# hand_rev_1_3_c.net
KiCad netlist of a schematic drawn in EAGLE
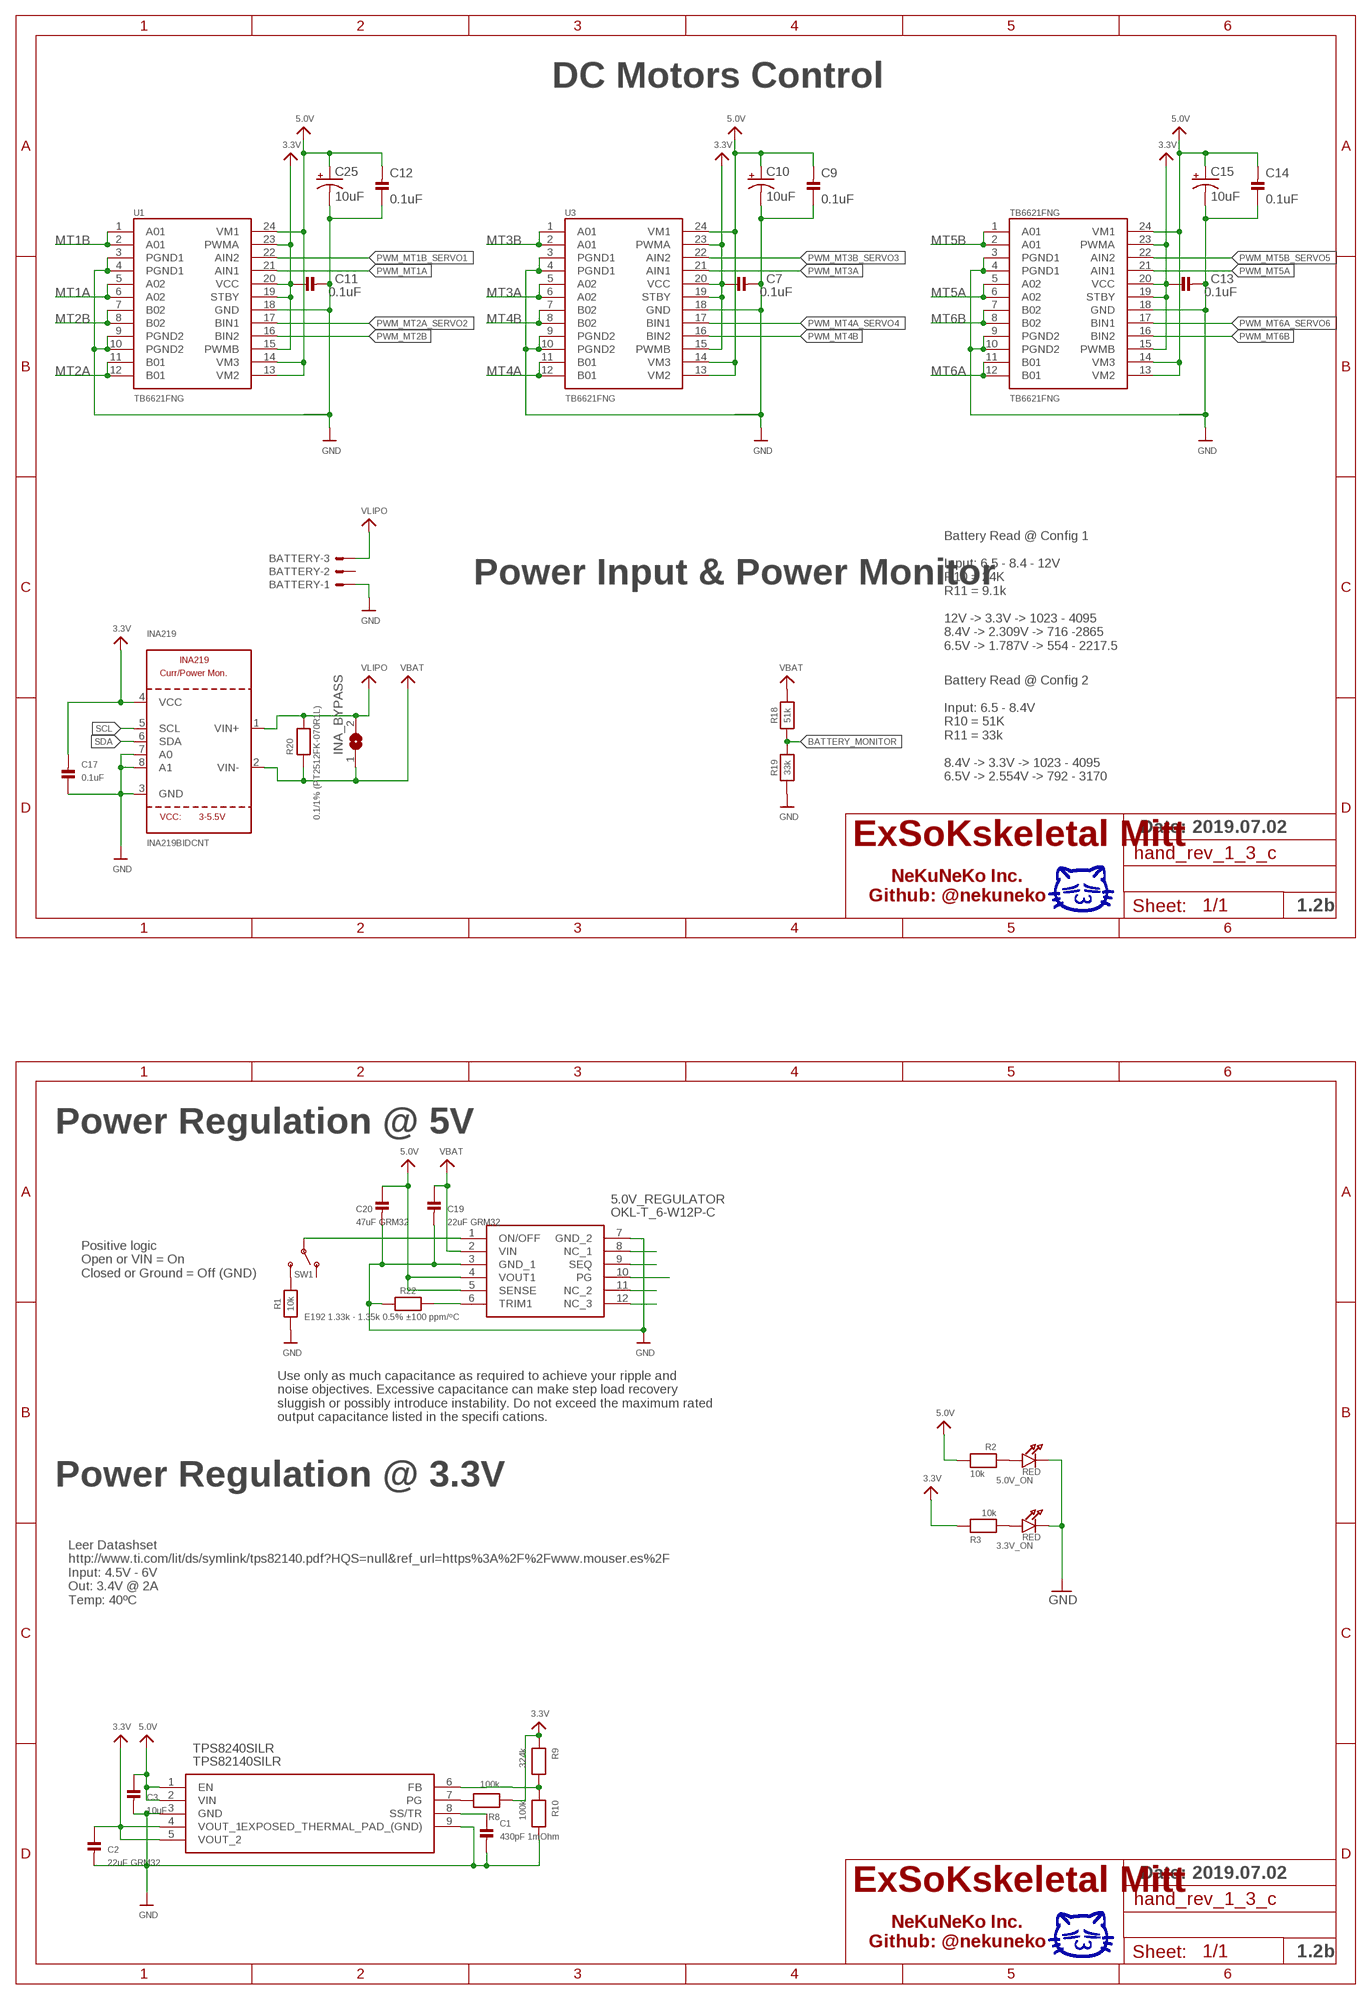
[diagram p0: schematic, sheet 1, part 1 of 2]
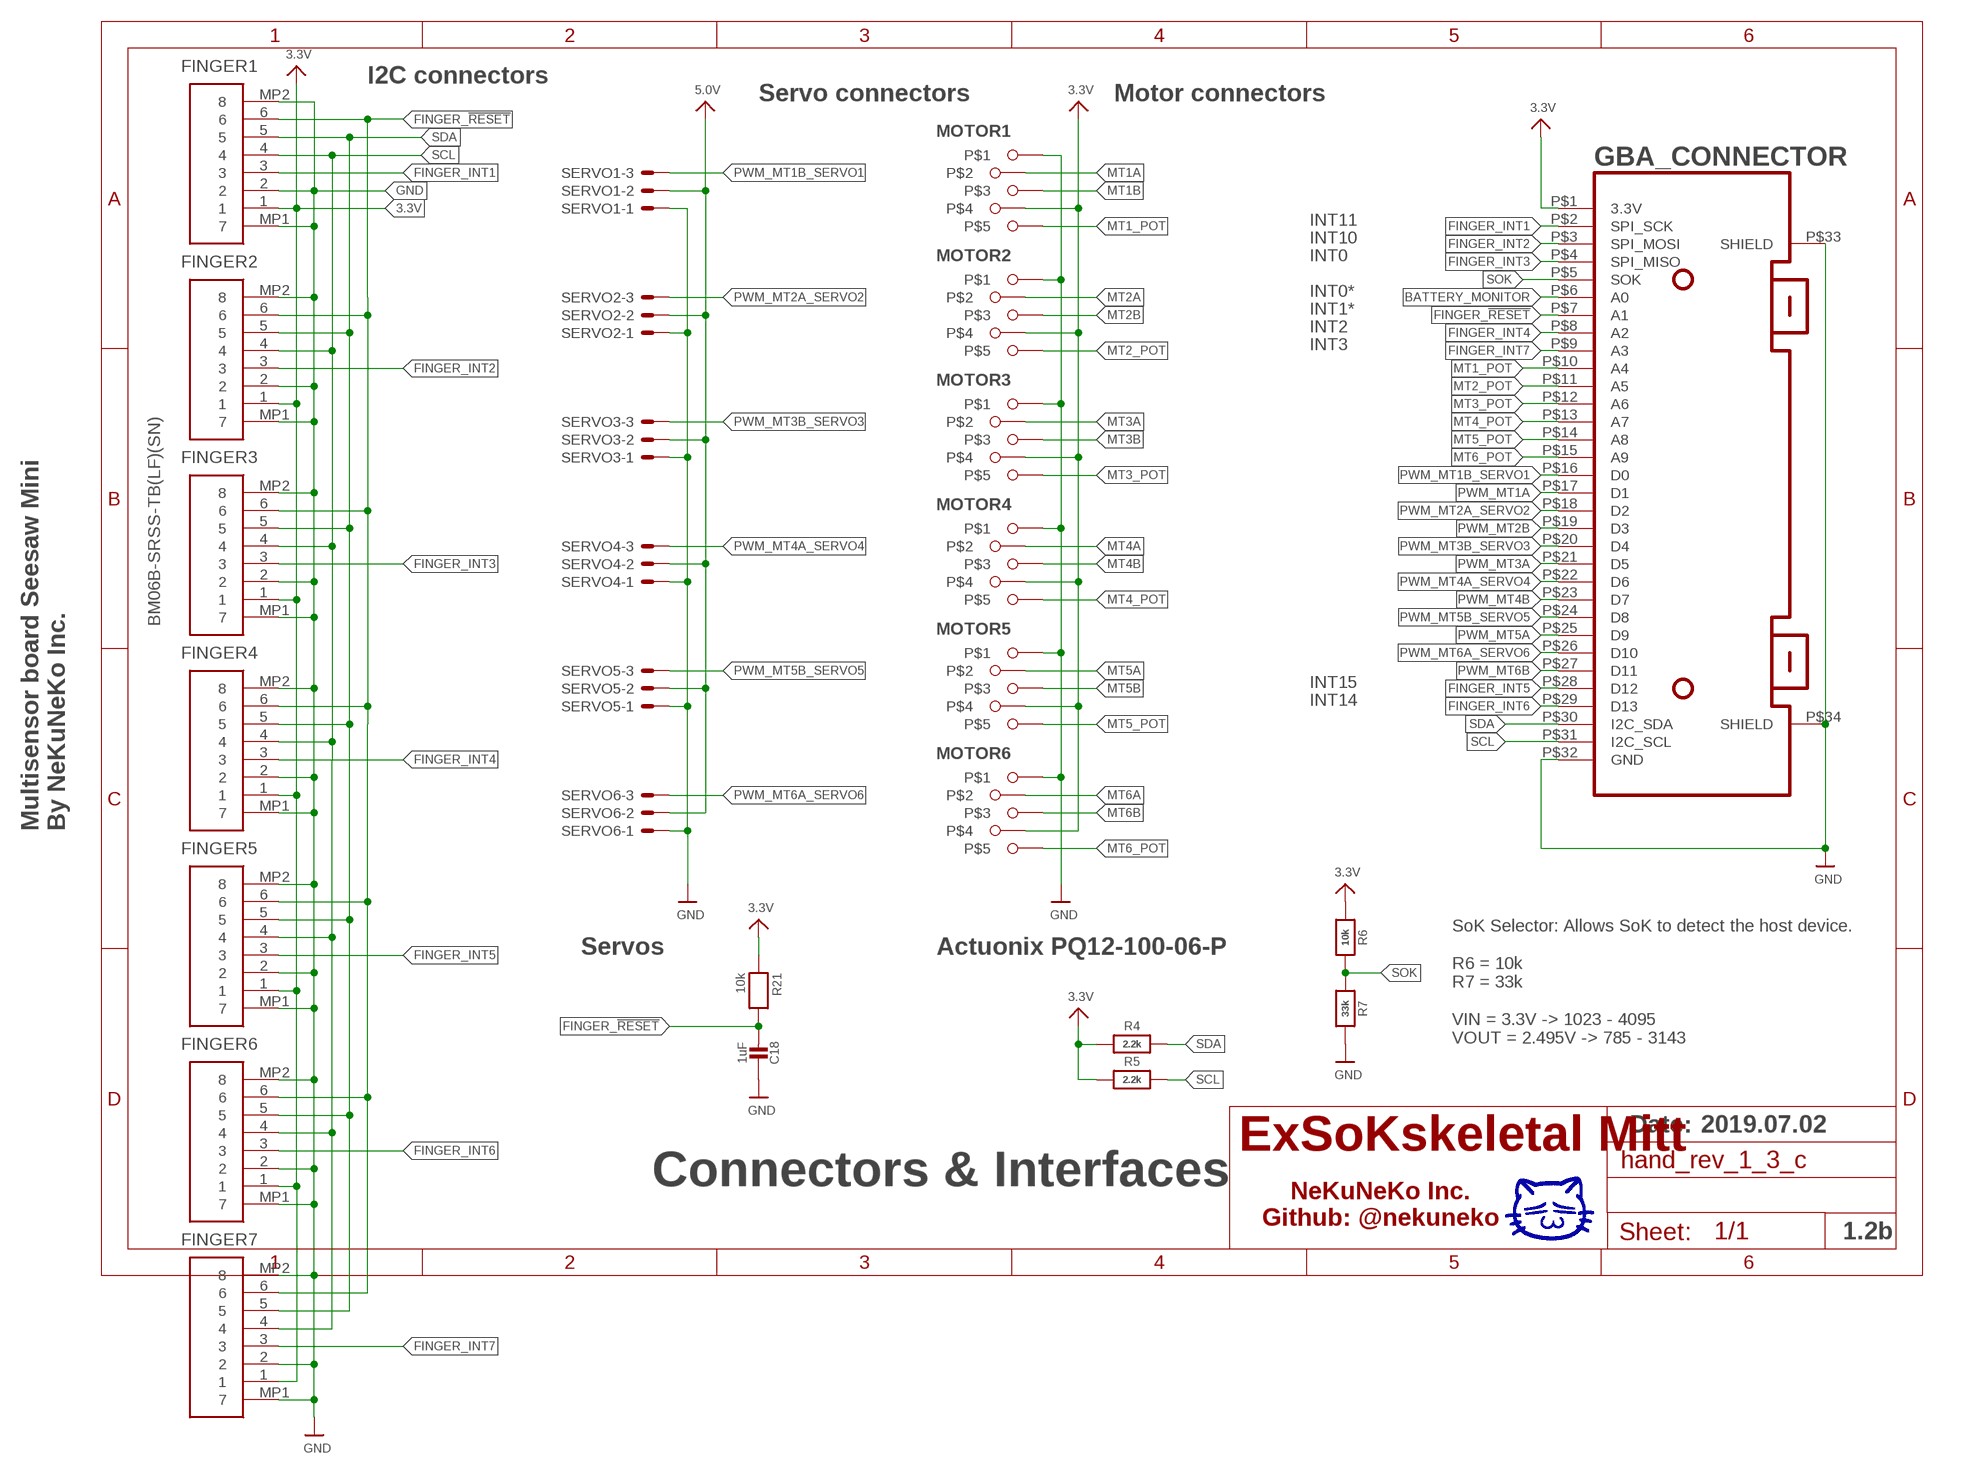
[diagram p1: schematic, sheet 1, part 2 of 2]

(export (version "E")
  (design (tool "Eeschema 10.0.6"))
  (components
    (comp (ref "3.3V_ON")
      (value "RED")
      (footprint "eagle-import:CHIPLED_0603")
      (libsource (lib "eagle-import") (part "LED0603"))
    )
    (comp (ref "5.0V_ON")
      (value "RED")
      (footprint "eagle-import:CHIPLED_0603")
      (libsource (lib "eagle-import") (part "LED0603"))
    )
    (comp (ref "5.0V_REGULATOR")
      (value "OKL-T_6-W12P-C")
      (footprint "eagle-import:OKL-T3-W12")
      (fields
        (field (name "MANUFACTURER_PART_NUMBER") "OKL-T/6-W12P-C")
        (field (name "MOUSER_PART_NUMBER") "580-OKL-T/6-W12P-C")
      )
      (libsource (lib "eagle-import") (part "OKL-T_6-W12P-C"))
    )
    (comp (ref "BATTERY")
      (value "JST-XH-03-PIN-LONG-PAD")
      (footprint "eagle-import:JST-XH-03-PACKAGE-LONG-PAD")
      (libsource (lib "eagle-import") (part "JST-XH-03-PIN-LONG-PAD"))
    )
    (comp (ref "C1")
      (value "430pF 1mOhm")
      (footprint "eagle-import:_0402")
      (libsource (lib "eagle-import") (part "microbuilder_CAP_CERAMIC_0402"))
    )
    (comp (ref "C2")
      (value "22uF GRM32")
      (footprint "eagle-import:_0603")
      (libsource (lib "eagle-import") (part "microbuilder_CAP_CERAMIC_0603"))
    )
    (comp (ref "C3")
      (value "10uF")
      (footprint "eagle-import:_0603")
      (libsource (lib "eagle-import") (part "microbuilder_CAP_CERAMIC_0603"))
    )
    (comp (ref "C7")
      (value "0.1uF")
      (footprint "eagle-import:_0603")
      (libsource (lib "eagle-import") (part "microbuilder_CAP_CERAMIC_0603"))
    )
    (comp (ref "C9")
      (value "0.1uF")
      (footprint "eagle-import:_0603")
      (libsource (lib "eagle-import") (part "microbuilder_CAP_CERAMIC_0603"))
    )
    (comp (ref "C10")
      (value "10uF")
      (footprint "eagle-import:0603-POLAR")
      (fields (field (name "MPN") "F981A106MMA"))
      (libsource (lib "eagle-import") (part "10UF-POLAR-0603-6.3V-20%(TANT)"))
    )
    (comp (ref "C11")
      (value "0.1uF")
      (footprint "eagle-import:_0603")
      (libsource (lib "eagle-import") (part "microbuilder_CAP_CERAMIC_0603"))
    )
    (comp (ref "C12")
      (value "0.1uF")
      (footprint "eagle-import:_0603")
      (libsource (lib "eagle-import") (part "microbuilder_CAP_CERAMIC_0603"))
    )
    (comp (ref "C13")
      (value "0.1uF")
      (footprint "eagle-import:_0603")
      (libsource (lib "eagle-import") (part "microbuilder_CAP_CERAMIC_0603"))
    )
    (comp (ref "C14")
      (value "0.1uF")
      (footprint "eagle-import:_0603")
      (libsource (lib "eagle-import") (part "microbuilder_CAP_CERAMIC_0603"))
    )
    (comp (ref "C15")
      (value "10uF")
      (footprint "eagle-import:0603-POLAR")
      (fields (field (name "MPN") "F981A106MMA"))
      (libsource (lib "eagle-import") (part "10UF-POLAR-0603-6.3V-20%(TANT)"))
    )
    (comp (ref "C17")
      (value "0.1uF")
      (footprint "eagle-import:_0603")
      (libsource (lib "eagle-import") (part "microbuilder_CAP_CERAMIC_0603"))
    )
    (comp (ref "C18")
      (value "1uF")
      (footprint "eagle-import:MICROBUILDER__0603")
      (libsource (lib "eagle-import") (part "CAP_CERAMIC_0603"))
    )
    (comp (ref "C19")
      (value "22uF GRM32")
      (footprint "eagle-import:0805")
      (libsource (lib "eagle-import") (part "CAP_CERAMIC0805"))
    )
    (comp (ref "C20")
      (value "47uF GRM32")
      (footprint "eagle-import:0805")
      (libsource (lib "eagle-import") (part "CAP_CERAMIC0805"))
    )
    (comp (ref "C25")
      (value "10uF")
      (footprint "eagle-import:0603-POLAR")
      (fields (field (name "MPN") "F981A106MMA"))
      (libsource (lib "eagle-import") (part "10UF-POLAR-0603-6.3V-20%(TANT)"))
    )
    (comp (ref "FINGER1")
      (value "BM06B-SRSS-TB(LF)(SN)")
      (footprint "eagle-import:BM06BSRSSTBLFSN")
      (fields (field (name "RS_PART_NUMBER") "5468782"))
      (libsource (lib "eagle-import") (part "BM06B-SRSS-TB(LF)(SN)"))
    )
    (comp (ref "FINGER2")
      (value "BM06B-SRSS-TB(LF)(SN)")
      (footprint "eagle-import:BM06BSRSSTBLFSN")
      (fields (field (name "RS_PART_NUMBER") "5468782"))
      (libsource (lib "eagle-import") (part "BM06B-SRSS-TB(LF)(SN)"))
    )
    (comp (ref "FINGER3")
      (value "BM06B-SRSS-TB(LF)(SN)")
      (footprint "eagle-import:BM06BSRSSTBLFSN")
      (fields (field (name "RS_PART_NUMBER") "5468782"))
      (libsource (lib "eagle-import") (part "BM06B-SRSS-TB(LF)(SN)"))
    )
    (comp (ref "FINGER4")
      (value "BM06B-SRSS-TB(LF)(SN)")
      (footprint "eagle-import:BM06BSRSSTBLFSN")
      (fields (field (name "RS_PART_NUMBER") "5468782"))
      (libsource (lib "eagle-import") (part "BM06B-SRSS-TB(LF)(SN)"))
    )
    (comp (ref "FINGER5")
      (value "BM06B-SRSS-TB(LF)(SN)")
      (footprint "eagle-import:BM06BSRSSTBLFSN")
      (fields (field (name "RS_PART_NUMBER") "5468782"))
      (libsource (lib "eagle-import") (part "BM06B-SRSS-TB(LF)(SN)"))
    )
    (comp (ref "FINGER6")
      (value "BM06B-SRSS-TB(LF)(SN)")
      (footprint "eagle-import:BM06BSRSSTBLFSN")
      (fields (field (name "RS_PART_NUMBER") "5468782"))
      (libsource (lib "eagle-import") (part "BM06B-SRSS-TB(LF)(SN)"))
    )
    (comp (ref "FINGER7")
      (value "BM06B-SRSS-TB(LF)(SN)")
      (footprint "eagle-import:BM06BSRSSTBLFSN")
      (fields (field (name "RS_PART_NUMBER") "5468782"))
      (libsource (lib "eagle-import") (part "BM06B-SRSS-TB(LF)(SN)"))
    )
    (comp (ref "GBA_CONNECTOR")
      (value "GBA_CARTRIDGEGBA_CARTRIDGE2")
      (footprint "eagle-import:GBA_CARTRIDGE2")
      (libsource (lib "eagle-import") (part "GBA_CARTRIDGEGBA_CARTRIDGE2"))
    )
    (comp (ref "INA219")
      (value "INA219BIDCNT")
      (footprint "eagle-import:SOT23-8")
      (libsource (lib "eagle-import") (part "INA219"))
    )
    (comp (ref "INA_BYPASS")
      (value "SOLDERJUMPERREFLOW_NOPASTE")
      (footprint "eagle-import:SOLDERJUMPER_REFLOW_NOPASTE")
      (libsource (lib "eagle-import") (part "SOLDERJUMPERREFLOW_NOPASTE"))
    )
    (comp (ref "MOTOR1")
      (value "Actuonix PQ12-100-06-P")
      (footprint "eagle-import:5PIN")
      (libsource (lib "eagle-import") (part "5PIN"))
    )
    (comp (ref "MOTOR2")
      (value "Actuonix PQ12-100-06-P")
      (footprint "eagle-import:5PIN")
      (libsource (lib "eagle-import") (part "5PIN"))
    )
    (comp (ref "MOTOR3")
      (value "Actuonix PQ12-100-06-P")
      (footprint "eagle-import:5PIN")
      (libsource (lib "eagle-import") (part "5PIN"))
    )
    (comp (ref "MOTOR4")
      (value "Actuonix PQ12-100-06-P")
      (footprint "eagle-import:5PIN")
      (libsource (lib "eagle-import") (part "5PIN"))
    )
    (comp (ref "MOTOR5")
      (value "Actuonix PQ12-100-06-P")
      (footprint "eagle-import:5PIN")
      (libsource (lib "eagle-import") (part "5PIN"))
    )
    (comp (ref "MOTOR6")
      (value "Actuonix PQ12-100-06-P")
      (footprint "eagle-import:5PIN")
      (libsource (lib "eagle-import") (part "5PIN"))
    )
    (comp (ref "R1")
      (value "10k")
      (footprint "eagle-import:_0603")
      (libsource (lib "eagle-import") (part "RESISTOR_0603"))
    )
    (comp (ref "R2")
      (value "10k")
      (footprint "eagle-import:_0603")
      (libsource (lib "eagle-import") (part "RESISTOR_0603"))
    )
    (comp (ref "R3")
      (value "10k")
      (footprint "eagle-import:_0603")
      (libsource (lib "eagle-import") (part "RESISTOR_0603"))
    )
    (comp (ref "R4")
      (value "2.2k")
      (footprint "eagle-import:_0603")
      (libsource (lib "eagle-import") (part "RESISTOR_0603"))
    )
    (comp (ref "R5")
      (value "2.2k")
      (footprint "eagle-import:_0603")
      (libsource (lib "eagle-import") (part "RESISTOR_0603"))
    )
    (comp (ref "R6")
      (value "10k")
      (footprint "eagle-import:_0603")
      (libsource (lib "eagle-import") (part "RESISTOR_0603"))
    )
    (comp (ref "R7")
      (value "33k")
      (footprint "eagle-import:_0603")
      (libsource (lib "eagle-import") (part "RESISTOR_0603"))
    )
    (comp (ref "R8")
      (value "100k")
      (footprint "eagle-import:_0402")
      (libsource (lib "eagle-import") (part "RESISTOR_0402"))
    )
    (comp (ref "R9")
      (value "324k")
      (footprint "eagle-import:_0402")
      (libsource (lib "eagle-import") (part "RESISTOR_0402"))
    )
    (comp (ref "R10")
      (value "100k")
      (footprint "eagle-import:_0402")
      (libsource (lib "eagle-import") (part "RESISTOR_0402"))
    )
    (comp (ref "R18")
      (value "51k")
      (footprint "eagle-import:_0603")
      (libsource (lib "eagle-import") (part "RESISTOR_0603"))
    )
    (comp (ref "R19")
      (value "33k")
      (footprint "eagle-import:_0603")
      (libsource (lib "eagle-import") (part "RESISTOR_0603"))
    )
    (comp (ref "R20")
      (value "0.1/1% (PT2512FK-070R1L)")
      (footprint "eagle-import:2512")
      (libsource (lib "eagle-import") (part "RESISTOR2512"))
    )
    (comp (ref "R21")
      (value "10k")
      (footprint "eagle-import:_0603")
      (libsource (lib "eagle-import") (part "RESISTOR_0603"))
    )
    (comp (ref "R22")
      (value "E192 1.33k - 1.35k 0.5% ±100 ppm/ºC")
      (footprint "eagle-import:_0603")
      (libsource (lib "eagle-import") (part "RESISTOR_0603"))
    )
    (comp (ref "SERVO1")
      (value "JST-XH-03-PIN-LONG-PAD")
      (footprint "eagle-import:JST-XH-03-PACKAGE-LONG-PAD")
      (libsource (lib "eagle-import") (part "JST-XH-03-PIN-LONG-PAD"))
    )
    (comp (ref "SERVO2")
      (value "JST-XH-03-PIN-LONG-PAD")
      (footprint "eagle-import:JST-XH-03-PACKAGE-LONG-PAD")
      (libsource (lib "eagle-import") (part "JST-XH-03-PIN-LONG-PAD"))
    )
    (comp (ref "SERVO3")
      (value "JST-XH-03-PIN-LONG-PAD")
      (footprint "eagle-import:JST-XH-03-PACKAGE-LONG-PAD")
      (libsource (lib "eagle-import") (part "JST-XH-03-PIN-LONG-PAD"))
    )
    (comp (ref "SERVO4")
      (value "JST-XH-03-PIN-LONG-PAD")
      (footprint "eagle-import:JST-XH-03-PACKAGE-LONG-PAD")
      (libsource (lib "eagle-import") (part "JST-XH-03-PIN-LONG-PAD"))
    )
    (comp (ref "SERVO5")
      (value "JST-XH-03-PIN-LONG-PAD")
      (footprint "eagle-import:JST-XH-03-PACKAGE-LONG-PAD")
      (libsource (lib "eagle-import") (part "JST-XH-03-PIN-LONG-PAD"))
    )
    (comp (ref "SERVO6")
      (value "JST-XH-03-PIN-LONG-PAD")
      (footprint "eagle-import:JST-XH-03-PACKAGE-LONG-PAD")
      (libsource (lib "eagle-import") (part "JST-XH-03-PIN-LONG-PAD"))
    )
    (comp (ref "SW1")
      (value "SWITCH_SPDT")
      (footprint "eagle-import:SPDT_SMT_SSSS811101")
      (libsource (lib "eagle-import") (part "SWITCH_SPDT"))
    )
    (comp (ref "TB6621FNG")
      (value "TB6621FNG")
      (footprint "eagle-import:SSOP24")
      (libsource (lib "eagle-import") (part "TB6621FNG"))
    )
    (comp (ref "TPS8240SILR")
      (value "TPS82140SILR")
      (footprint "eagle-import:SIL0008D")
      (fields (field (name "MOUSER_PART_NUMBER") "595-TPS82140SILR"))
      (libsource (lib "eagle-import") (part "TPS82140SILR"))
    )
    (comp (ref "U1")
      (value "TB6621FNG")
      (footprint "eagle-import:SSOP24")
      (libsource (lib "eagle-import") (part "TB6621FNG"))
    )
    (comp (ref "U3")
      (value "TB6621FNG")
      (footprint "eagle-import:SSOP24")
      (libsource (lib "eagle-import") (part "TB6621FNG"))
    )
  )
  (nets
    (net (code "1") (name "/FINGER_~{RESET}") (class "Default")
      (node (ref "C18") (pin "2") (pinfunction "2_2") (pintype "passive"))
      (node (ref "FINGER1") (pin "6") (pinfunction "6_6") (pintype "bidirectional"))
      (node (ref "FINGER2") (pin "6") (pinfunction "6_6") (pintype "bidirectional"))
      (node (ref "FINGER3") (pin "6") (pinfunction "6_6") (pintype "bidirectional"))
      (node (ref "FINGER4") (pin "6") (pinfunction "6_6") (pintype "bidirectional"))
      (node (ref "FINGER5") (pin "6") (pinfunction "6_6") (pintype "bidirectional"))
      (node (ref "FINGER6") (pin "6") (pinfunction "6_6") (pintype "bidirectional"))
      (node (ref "FINGER7") (pin "6") (pinfunction "6_6") (pintype "bidirectional"))
      (node (ref "GBA_CONNECTOR") (pin "P$7") (pinfunction "A1_P$7") (pintype "bidirectional"))
      (node (ref "R21") (pin "2") (pinfunction "2_2") (pintype "passive"))
    )
    (net (code "2") (name "3.3V") (class "Default")
      (node (ref "C11") (pin "1") (pinfunction "P$1_1") (pintype "passive"))
      (node (ref "C13") (pin "1") (pinfunction "P$1_1") (pintype "passive"))
      (node (ref "C17") (pin "2") (pinfunction "P$2_2") (pintype "passive"))
      (node (ref "C2") (pin "1") (pinfunction "P$1_1") (pintype "passive"))
      (node (ref "C7") (pin "1") (pinfunction "P$1_1") (pintype "passive"))
      (node (ref "FINGER1") (pin "1") (pinfunction "1_1") (pintype "bidirectional"))
      (node (ref "FINGER2") (pin "1") (pinfunction "1_1") (pintype "bidirectional"))
      (node (ref "FINGER3") (pin "1") (pinfunction "1_1") (pintype "bidirectional"))
      (node (ref "FINGER4") (pin "1") (pinfunction "1_1") (pintype "bidirectional"))
      (node (ref "FINGER5") (pin "1") (pinfunction "1_1") (pintype "bidirectional"))
      (node (ref "FINGER6") (pin "1") (pinfunction "1_1") (pintype "bidirectional"))
      (node (ref "FINGER7") (pin "1") (pinfunction "1_1") (pintype "bidirectional"))
      (node (ref "GBA_CONNECTOR") (pin "P$1") (pinfunction "3.3V_P$1") (pintype "power_in"))
      (node (ref "INA219") (pin "4") (pinfunction "VCC_4") (pintype "bidirectional"))
      (node (ref "MOTOR1") (pin "4") (pinfunction "P$4_4") (pintype "bidirectional"))
      (node (ref "MOTOR2") (pin "4") (pinfunction "P$4_4") (pintype "bidirectional"))
      (node (ref "MOTOR3") (pin "4") (pinfunction "P$4_4") (pintype "bidirectional"))
      (node (ref "MOTOR4") (pin "4") (pinfunction "P$4_4") (pintype "bidirectional"))
      (node (ref "MOTOR5") (pin "4") (pinfunction "P$4_4") (pintype "bidirectional"))
      (node (ref "MOTOR6") (pin "4") (pinfunction "P$4_4") (pintype "bidirectional"))
      (node (ref "R21") (pin "1") (pinfunction "1_1") (pintype "passive"))
      (node (ref "R3") (pin "1") (pinfunction "1_1") (pintype "passive"))
      (node (ref "R4") (pin "1") (pinfunction "1_1") (pintype "passive"))
      (node (ref "R5") (pin "1") (pinfunction "1_1") (pintype "passive"))
      (node (ref "R6") (pin "1") (pinfunction "1_1") (pintype "passive"))
      (node (ref "R8") (pin "1") (pinfunction "1_1") (pintype "passive"))
      (node (ref "R9") (pin "1") (pinfunction "1_1") (pintype "passive"))
      (node (ref "TB6621FNG") (pin "15") (pinfunction "PWMB_15") (pintype "bidirectional"))
      (node (ref "TB6621FNG") (pin "19") (pinfunction "STBY_19") (pintype "bidirectional"))
      (node (ref "TB6621FNG") (pin "20") (pinfunction "VCC_20") (pintype "bidirectional"))
      (node (ref "TB6621FNG") (pin "23") (pinfunction "PWMA_23") (pintype "bidirectional"))
      (node (ref "TPS8240SILR") (pin "4") (pinfunction "VOUT_1_4") (pintype "bidirectional"))
      (node (ref "TPS8240SILR") (pin "5") (pinfunction "VOUT_2_5") (pintype "bidirectional"))
      (node (ref "U1") (pin "15") (pinfunction "PWMB_15") (pintype "bidirectional"))
      (node (ref "U1") (pin "19") (pinfunction "STBY_19") (pintype "bidirectional"))
      (node (ref "U1") (pin "20") (pinfunction "VCC_20") (pintype "bidirectional"))
      (node (ref "U1") (pin "23") (pinfunction "PWMA_23") (pintype "bidirectional"))
      (node (ref "U3") (pin "15") (pinfunction "PWMB_15") (pintype "bidirectional"))
      (node (ref "U3") (pin "19") (pinfunction "STBY_19") (pintype "bidirectional"))
      (node (ref "U3") (pin "20") (pinfunction "VCC_20") (pintype "bidirectional"))
      (node (ref "U3") (pin "23") (pinfunction "PWMA_23") (pintype "bidirectional"))
    )
    (net (code "3") (name "5.0V") (class "Default")
      (node (ref "5.0V_REGULATOR") (pin "4") (pinfunction "VOUT1_4") (pintype "bidirectional"))
      (node (ref "5.0V_REGULATOR") (pin "5") (pinfunction "SENSE_5") (pintype "bidirectional"))
      (node (ref "C10") (pin "+") (pinfunction "+_+") (pintype "passive"))
      (node (ref "C12") (pin "2") (pinfunction "P$2_2") (pintype "passive"))
      (node (ref "C14") (pin "2") (pinfunction "P$2_2") (pintype "passive"))
      (node (ref "C15") (pin "+") (pinfunction "+_+") (pintype "passive"))
      (node (ref "C20") (pin "1") (pinfunction "P$1_1") (pintype "passive"))
      (node (ref "C25") (pin "+") (pinfunction "+_+") (pintype "passive"))
      (node (ref "C3") (pin "1") (pinfunction "P$1_1") (pintype "passive"))
      (node (ref "C9") (pin "2") (pinfunction "P$2_2") (pintype "passive"))
      (node (ref "R2") (pin "2") (pinfunction "2_2") (pintype "passive"))
      (node (ref "SERVO1") (pin "2") (pinfunction "S_2") (pintype "passive"))
      (node (ref "SERVO2") (pin "2") (pinfunction "S_2") (pintype "passive"))
      (node (ref "SERVO3") (pin "2") (pinfunction "S_2") (pintype "passive"))
      (node (ref "SERVO4") (pin "2") (pinfunction "S_2") (pintype "passive"))
      (node (ref "SERVO5") (pin "2") (pinfunction "S_2") (pintype "passive"))
      (node (ref "SERVO6") (pin "2") (pinfunction "S_2") (pintype "passive"))
      (node (ref "TB6621FNG") (pin "13") (pinfunction "VM2_13") (pintype "bidirectional"))
      (node (ref "TB6621FNG") (pin "14") (pinfunction "VM3_14") (pintype "bidirectional"))
      (node (ref "TB6621FNG") (pin "24") (pinfunction "VM1_24") (pintype "bidirectional"))
      (node (ref "TPS8240SILR") (pin "1") (pinfunction "EN_1") (pintype "bidirectional"))
      (node (ref "TPS8240SILR") (pin "2") (pinfunction "VIN_2") (pintype "bidirectional"))
      (node (ref "U1") (pin "13") (pinfunction "VM2_13") (pintype "bidirectional"))
      (node (ref "U1") (pin "14") (pinfunction "VM3_14") (pintype "bidirectional"))
      (node (ref "U1") (pin "24") (pinfunction "VM1_24") (pintype "bidirectional"))
      (node (ref "U3") (pin "13") (pinfunction "VM2_13") (pintype "bidirectional"))
      (node (ref "U3") (pin "14") (pinfunction "VM3_14") (pintype "bidirectional"))
      (node (ref "U3") (pin "24") (pinfunction "VM1_24") (pintype "bidirectional"))
    )
    (net (code "4") (name "BATTERY_MONITOR") (class "Default")
      (node (ref "GBA_CONNECTOR") (pin "P$6") (pinfunction "A0_P$6") (pintype "bidirectional"))
      (node (ref "R18") (pin "1") (pinfunction "1_1") (pintype "passive"))
      (node (ref "R19") (pin "2") (pinfunction "2_2") (pintype "passive"))
    )
    (net (code "5") (name "FINGER_INT1") (class "Default")
      (node (ref "FINGER1") (pin "3") (pinfunction "3_3") (pintype "bidirectional"))
      (node (ref "GBA_CONNECTOR") (pin "P$2") (pinfunction "SPI_SCK_P$2") (pintype "bidirectional"))
    )
    (net (code "6") (name "FINGER_INT2") (class "Default")
      (node (ref "FINGER2") (pin "3") (pinfunction "3_3") (pintype "bidirectional"))
      (node (ref "GBA_CONNECTOR") (pin "P$3") (pinfunction "SPI_MOSI_P$3") (pintype "bidirectional"))
    )
    (net (code "7") (name "FINGER_INT3") (class "Default")
      (node (ref "FINGER3") (pin "3") (pinfunction "3_3") (pintype "bidirectional"))
      (node (ref "GBA_CONNECTOR") (pin "P$4") (pinfunction "SPI_MISO_P$4") (pintype "bidirectional"))
    )
    (net (code "8") (name "FINGER_INT4") (class "Default")
      (node (ref "FINGER4") (pin "3") (pinfunction "3_3") (pintype "bidirectional"))
      (node (ref "GBA_CONNECTOR") (pin "P$8") (pinfunction "A2_P$8") (pintype "bidirectional"))
    )
    (net (code "9") (name "FINGER_INT5") (class "Default")
      (node (ref "FINGER5") (pin "3") (pinfunction "3_3") (pintype "bidirectional"))
      (node (ref "GBA_CONNECTOR") (pin "P$28") (pinfunction "D12_P$28") (pintype "bidirectional"))
    )
    (net (code "10") (name "FINGER_INT6") (class "Default")
      (node (ref "FINGER6") (pin "3") (pinfunction "3_3") (pintype "bidirectional"))
      (node (ref "GBA_CONNECTOR") (pin "P$29") (pinfunction "D13_P$29") (pintype "bidirectional"))
    )
    (net (code "11") (name "FINGER_INT7") (class "Default")
      (node (ref "FINGER7") (pin "3") (pinfunction "3_3") (pintype "bidirectional"))
      (node (ref "GBA_CONNECTOR") (pin "P$9") (pinfunction "A3_P$9") (pintype "bidirectional"))
    )
    (net (code "12") (name "GND") (class "Default")
      (node (ref "3.3V_ON") (pin "C") (pinfunction "C_C") (pintype "passive"))
      (node (ref "5.0V_ON") (pin "C") (pinfunction "C_C") (pintype "passive"))
      (node (ref "5.0V_REGULATOR") (pin "3") (pinfunction "GND_1_3") (pintype "bidirectional"))
      (node (ref "5.0V_REGULATOR") (pin "7") (pinfunction "GND_2_7") (pintype "bidirectional"))
      (node (ref "BATTERY") (pin "1") (pinfunction "S_1") (pintype "passive"))
      (node (ref "C1") (pin "2") (pinfunction "P$2_2") (pintype "passive"))
      (node (ref "C10") (pin "-") (pinfunction "-_-") (pintype "passive"))
      (node (ref "C11") (pin "2") (pinfunction "P$2_2") (pintype "passive"))
      (node (ref "C12") (pin "1") (pinfunction "P$1_1") (pintype "passive"))
      (node (ref "C13") (pin "2") (pinfunction "P$2_2") (pintype "passive"))
      (node (ref "C14") (pin "1") (pinfunction "P$1_1") (pintype "passive"))
      (node (ref "C15") (pin "-") (pinfunction "-_-") (pintype "passive"))
      (node (ref "C17") (pin "1") (pinfunction "P$1_1") (pintype "passive"))
      (node (ref "C18") (pin "1") (pinfunction "1_1") (pintype "passive"))
      (node (ref "C19") (pin "2") (pinfunction "P$2_2") (pintype "passive"))
      (node (ref "C2") (pin "2") (pinfunction "P$2_2") (pintype "passive"))
      (node (ref "C20") (pin "2") (pinfunction "P$2_2") (pintype "passive"))
      (node (ref "C25") (pin "-") (pinfunction "-_-") (pintype "passive"))
      (node (ref "C3") (pin "2") (pinfunction "P$2_2") (pintype "passive"))
      (node (ref "C7") (pin "2") (pinfunction "P$2_2") (pintype "passive"))
      (node (ref "C9") (pin "1") (pinfunction "P$1_1") (pintype "passive"))
      (node (ref "FINGER1") (pin "2") (pinfunction "2_2") (pintype "bidirectional"))
      (node (ref "FINGER1") (pin "MP1") (pinfunction "7_MP1") (pintype "bidirectional"))
      (node (ref "FINGER1") (pin "MP2") (pinfunction "8_MP2") (pintype "bidirectional"))
      (node (ref "FINGER2") (pin "2") (pinfunction "2_2") (pintype "bidirectional"))
      (node (ref "FINGER2") (pin "MP1") (pinfunction "7_MP1") (pintype "bidirectional"))
      (node (ref "FINGER2") (pin "MP2") (pinfunction "8_MP2") (pintype "bidirectional"))
      (node (ref "FINGER3") (pin "2") (pinfunction "2_2") (pintype "bidirectional"))
      (node (ref "FINGER3") (pin "MP1") (pinfunction "7_MP1") (pintype "bidirectional"))
      (node (ref "FINGER3") (pin "MP2") (pinfunction "8_MP2") (pintype "bidirectional"))
      (node (ref "FINGER4") (pin "2") (pinfunction "2_2") (pintype "bidirectional"))
      (node (ref "FINGER4") (pin "MP1") (pinfunction "7_MP1") (pintype "bidirectional"))
      (node (ref "FINGER4") (pin "MP2") (pinfunction "8_MP2") (pintype "bidirectional"))
      (node (ref "FINGER5") (pin "2") (pinfunction "2_2") (pintype "bidirectional"))
      (node (ref "FINGER5") (pin "MP1") (pinfunction "7_MP1") (pintype "bidirectional"))
      (node (ref "FINGER5") (pin "MP2") (pinfunction "8_MP2") (pintype "bidirectional"))
      (node (ref "FINGER6") (pin "2") (pinfunction "2_2") (pintype "bidirectional"))
      (node (ref "FINGER6") (pin "MP1") (pinfunction "7_MP1") (pintype "bidirectional"))
      (node (ref "FINGER6") (pin "MP2") (pinfunction "8_MP2") (pintype "bidirectional"))
      (node (ref "FINGER7") (pin "2") (pinfunction "2_2") (pintype "bidirectional"))
      (node (ref "FINGER7") (pin "MP1") (pinfunction "7_MP1") (pintype "bidirectional"))
      (node (ref "FINGER7") (pin "MP2") (pinfunction "8_MP2") (pintype "bidirectional"))
      (node (ref "GBA_CONNECTOR") (pin "P$32") (pinfunction "GND_P$32") (pintype "power_in"))
      (node (ref "GBA_CONNECTOR") (pin "P$33") (pinfunction "SHIELD_P$33") (pintype "bidirectional"))
      (node (ref "GBA_CONNECTOR") (pin "P$34") (pinfunction "SHIELD_P$34") (pintype "bidirectional"))
      (node (ref "INA219") (pin "3") (pinfunction "GND_3") (pintype "bidirectional"))
      (node (ref "INA219") (pin "7") (pinfunction "A0_7") (pintype "bidirectional"))
      (node (ref "INA219") (pin "8") (pinfunction "A1_8") (pintype "bidirectional"))
      (node (ref "MOTOR1") (pin "1") (pinfunction "P$1_1") (pintype "bidirectional"))
      (node (ref "MOTOR2") (pin "1") (pinfunction "P$1_1") (pintype "bidirectional"))
      (node (ref "MOTOR3") (pin "1") (pinfunction "P$1_1") (pintype "bidirectional"))
      (node (ref "MOTOR4") (pin "1") (pinfunction "P$1_1") (pintype "bidirectional"))
      (node (ref "MOTOR5") (pin "1") (pinfunction "P$1_1") (pintype "bidirectional"))
      (node (ref "MOTOR6") (pin "1") (pinfunction "P$1_1") (pintype "bidirectional"))
      (node (ref "R1") (pin "1") (pinfunction "1_1") (pintype "passive"))
      (node (ref "R10") (pin "2") (pinfunction "2_2") (pintype "passive"))
      (node (ref "R19") (pin "1") (pinfunction "1_1") (pintype "passive"))
      (node (ref "R22") (pin "2") (pinfunction "2_2") (pintype "passive"))
      (node (ref "R7") (pin "2") (pinfunction "2_2") (pintype "passive"))
      (node (ref "SERVO1") (pin "1") (pinfunction "S_1") (pintype "passive"))
      (node (ref "SERVO2") (pin "1") (pinfunction "S_1") (pintype "passive"))
      (node (ref "SERVO3") (pin "1") (pinfunction "S_1") (pintype "passive"))
      (node (ref "SERVO4") (pin "1") (pinfunction "S_1") (pintype "passive"))
      (node (ref "SERVO5") (pin "1") (pinfunction "S_1") (pintype "passive"))
      (node (ref "SERVO6") (pin "1") (pinfunction "S_1") (pintype "passive"))
      (node (ref "TB6621FNG") (pin "10") (pinfunction "PGND2_10") (pintype "bidirectional"))
      (node (ref "TB6621FNG") (pin "18") (pinfunction "GND_18") (pintype "bidirectional"))
      (node (ref "TB6621FNG") (pin "3") (pinfunction "PGND1_3") (pintype "bidirectional"))
      (node (ref "TB6621FNG") (pin "4") (pinfunction "PGND1_4") (pintype "bidirectional"))
      (node (ref "TB6621FNG") (pin "9") (pinfunction "PGND2_9") (pintype "bidirectional"))
      (node (ref "TPS8240SILR") (pin "3") (pinfunction "GND_3") (pintype "bidirectional"))
      (node (ref "TPS8240SILR") (pin "9") (pinfunction "EXPOSED_THERMAL_PAD_(GND)_9") (pintype "bidirectional"))
      (node (ref "U1") (pin "10") (pinfunction "PGND2_10") (pintype "bidirectional"))
      (node (ref "U1") (pin "18") (pinfunction "GND_18") (pintype "bidirectional"))
      (node (ref "U1") (pin "3") (pinfunction "PGND1_3") (pintype "bidirectional"))
      (node (ref "U1") (pin "4") (pinfunction "PGND1_4") (pintype "bidirectional"))
      (node (ref "U1") (pin "9") (pinfunction "PGND2_9") (pintype "bidirectional"))
      (node (ref "U3") (pin "10") (pinfunction "PGND2_10") (pintype "bidirectional"))
      (node (ref "U3") (pin "18") (pinfunction "GND_18") (pintype "bidirectional"))
      (node (ref "U3") (pin "3") (pinfunction "PGND1_3") (pintype "bidirectional"))
      (node (ref "U3") (pin "4") (pinfunction "PGND1_4") (pintype "bidirectional"))
      (node (ref "U3") (pin "9") (pinfunction "PGND2_9") (pintype "bidirectional"))
    )
    (net (code "13") (name "MT1A") (class "Default")
      (node (ref "MOTOR1") (pin "2") (pinfunction "P$2_2") (pintype "bidirectional"))
      (node (ref "U1") (pin "5") (pinfunction "A02_5") (pintype "bidirectional"))
      (node (ref "U1") (pin "6") (pinfunction "A02_6") (pintype "bidirectional"))
    )
    (net (code "14") (name "MT1B") (class "Default")
      (node (ref "MOTOR1") (pin "3") (pinfunction "P$3_3") (pintype "bidirectional"))
      (node (ref "U1") (pin "1") (pinfunction "A01_1") (pintype "bidirectional"))
      (node (ref "U1") (pin "2") (pinfunction "A01_2") (pintype "bidirectional"))
    )
    (net (code "15") (name "MT1_POT") (class "Default")
      (node (ref "GBA_CONNECTOR") (pin "P$10") (pinfunction "A4_P$10") (pintype "bidirectional"))
      (node (ref "MOTOR1") (pin "5") (pinfunction "P$5_5") (pintype "bidirectional"))
    )
    (net (code "16") (name "MT2A") (class "Default")
      (node (ref "MOTOR2") (pin "2") (pinfunction "P$2_2") (pintype "bidirectional"))
      (node (ref "U1") (pin "11") (pinfunction "B01_11") (pintype "bidirectional"))
      (node (ref "U1") (pin "12") (pinfunction "B01_12") (pintype "bidirectional"))
    )
    (net (code "17") (name "MT2B") (class "Default")
      (node (ref "MOTOR2") (pin "3") (pinfunction "P$3_3") (pintype "bidirectional"))
      (node (ref "U1") (pin "7") (pinfunction "B02_7") (pintype "bidirectional"))
      (node (ref "U1") (pin "8") (pinfunction "B02_8") (pintype "bidirectional"))
    )
    (net (code "18") (name "MT2_POT") (class "Default")
      (node (ref "GBA_CONNECTOR") (pin "P$11") (pinfunction "A5_P$11") (pintype "bidirectional"))
      (node (ref "MOTOR2") (pin "5") (pinfunction "P$5_5") (pintype "bidirectional"))
    )
    (net (code "19") (name "MT3A") (class "Default")
      (node (ref "MOTOR3") (pin "2") (pinfunction "P$2_2") (pintype "bidirectional"))
      (node (ref "U3") (pin "5") (pinfunction "A02_5") (pintype "bidirectional"))
      (node (ref "U3") (pin "6") (pinfunction "A02_6") (pintype "bidirectional"))
    )
    (net (code "20") (name "MT3B") (class "Default")
      (node (ref "MOTOR3") (pin "3") (pinfunction "P$3_3") (pintype "bidirectional"))
      (node (ref "U3") (pin "1") (pinfunction "A01_1") (pintype "bidirectional"))
      (node (ref "U3") (pin "2") (pinfunction "A01_2") (pintype "bidirectional"))
    )
    (net (code "21") (name "MT3_POT") (class "Default")
      (node (ref "GBA_CONNECTOR") (pin "P$12") (pinfunction "A6_P$12") (pintype "bidirectional"))
      (node (ref "MOTOR3") (pin "5") (pinfunction "P$5_5") (pintype "bidirectional"))
    )
    (net (code "22") (name "MT4A") (class "Default")
      (node (ref "MOTOR4") (pin "2") (pinfunction "P$2_2") (pintype "bidirectional"))
      (node (ref "U3") (pin "11") (pinfunction "B01_11") (pintype "bidirectional"))
      (node (ref "U3") (pin "12") (pinfunction "B01_12") (pintype "bidirectional"))
    )
    (net (code "23") (name "MT4B") (class "Default")
      (node (ref "MOTOR4") (pin "3") (pinfunction "P$3_3") (pintype "bidirectional"))
      (node (ref "U3") (pin "7") (pinfunction "B02_7") (pintype "bidirectional"))
      (node (ref "U3") (pin "8") (pinfunction "B02_8") (pintype "bidirectional"))
    )
    (net (code "24") (name "MT4_POT") (class "Default")
      (node (ref "GBA_CONNECTOR") (pin "P$13") (pinfunction "A7_P$13") (pintype "bidirectional"))
      (node (ref "MOTOR4") (pin "5") (pinfunction "P$5_5") (pintype "bidirectional"))
    )
    (net (code "25") (name "MT5A") (class "Default")
      (node (ref "MOTOR5") (pin "2") (pinfunction "P$2_2") (pintype "bidirectional"))
      (node (ref "TB6621FNG") (pin "5") (pinfunction "A02_5") (pintype "bidirectional"))
      (node (ref "TB6621FNG") (pin "6") (pinfunction "A02_6") (pintype "bidirectional"))
    )
    (net (code "26") (name "MT5B") (class "Default")
      (node (ref "MOTOR5") (pin "3") (pinfunction "P$3_3") (pintype "bidirectional"))
      (node (ref "TB6621FNG") (pin "1") (pinfunction "A01_1") (pintype "bidirectional"))
      (node (ref "TB6621FNG") (pin "2") (pinfunction "A01_2") (pintype "bidirectional"))
    )
    (net (code "27") (name "MT5_POT") (class "Default")
      (node (ref "GBA_CONNECTOR") (pin "P$14") (pinfunction "A8_P$14") (pintype "bidirectional"))
      (node (ref "MOTOR5") (pin "5") (pinfunction "P$5_5") (pintype "bidirectional"))
    )
    (net (code "28") (name "MT6A") (class "Default")
      (node (ref "MOTOR6") (pin "2") (pinfunction "P$2_2") (pintype "bidirectional"))
      (node (ref "TB6621FNG") (pin "11") (pinfunction "B01_11") (pintype "bidirectional"))
      (node (ref "TB6621FNG") (pin "12") (pinfunction "B01_12") (pintype "bidirectional"))
    )
    (net (code "29") (name "MT6B") (class "Default")
      (node (ref "MOTOR6") (pin "3") (pinfunction "P$3_3") (pintype "bidirectional"))
      (node (ref "TB6621FNG") (pin "7") (pinfunction "B02_7") (pintype "bidirectional"))
      (node (ref "TB6621FNG") (pin "8") (pinfunction "B02_8") (pintype "bidirectional"))
    )
    (net (code "30") (name "MT6_POT") (class "Default")
      (node (ref "GBA_CONNECTOR") (pin "P$15") (pinfunction "A9_P$15") (pintype "bidirectional"))
      (node (ref "MOTOR6") (pin "5") (pinfunction "P$5_5") (pintype "bidirectional"))
    )
    (net (code "31") (name "Net-(3.3V_ON-PadA)") (class "Default")
      (node (ref "3.3V_ON") (pin "A") (pinfunction "A_A") (pintype "passive"))
      (node (ref "R3") (pin "2") (pinfunction "2_2") (pintype "passive"))
    )
    (net (code "32") (name "Net-(5.0V_ON-PadA)") (class "Default")
      (node (ref "5.0V_ON") (pin "A") (pinfunction "A_A") (pintype "passive"))
      (node (ref "R2") (pin "1") (pinfunction "1_1") (pintype "passive"))
    )
    (net (code "33") (name "Net-(5.0V_REGULATOR-ON{slash}OFF)") (class "Default")
      (node (ref "5.0V_REGULATOR") (pin "1") (pinfunction "ON/OFF_1") (pintype "bidirectional"))
      (node (ref "SW1") (pin "B") (pinfunction "P_B") (pintype "passive"))
    )
    (net (code "34") (name "Net-(5.0V_REGULATOR-TRIM1)") (class "Default")
      (node (ref "5.0V_REGULATOR") (pin "6") (pinfunction "TRIM1_6") (pintype "bidirectional"))
      (node (ref "R22") (pin "1") (pinfunction "1_1") (pintype "passive"))
    )
    (net (code "35") (name "Net-(C1-P$1)") (class "Default")
      (node (ref "C1") (pin "1") (pinfunction "P$1_1") (pintype "passive"))
      (node (ref "TPS8240SILR") (pin "8") (pinfunction "SS/TR_8") (pintype "bidirectional"))
    )
    (net (code "36") (name "Net-(SW1-S)") (class "Default")
      (node (ref "R1") (pin "2") (pinfunction "2_2") (pintype "passive"))
      (node (ref "SW1") (pin "C") (pinfunction "S_C") (pintype "passive"))
    )
    (net (code "37") (name "Net-(TPS8240SILR-FB)") (class "Default")
      (node (ref "R10") (pin "1") (pinfunction "1_1") (pintype "passive"))
      (node (ref "R9") (pin "2") (pinfunction "2_2") (pintype "passive"))
      (node (ref "TPS8240SILR") (pin "6") (pinfunction "FB_6") (pintype "bidirectional"))
    )
    (net (code "38") (name "Net-(TPS8240SILR-PG)") (class "Default")
      (node (ref "R8") (pin "2") (pinfunction "2_2") (pintype "passive"))
      (node (ref "TPS8240SILR") (pin "7") (pinfunction "PG_7") (pintype "bidirectional"))
    )
    (net (code "39") (name "PWM_MT1A") (class "Default")
      (node (ref "GBA_CONNECTOR") (pin "P$17") (pinfunction "D1_P$17") (pintype "bidirectional"))
      (node (ref "U1") (pin "21") (pinfunction "AIN1_21") (pintype "bidirectional"))
    )
    (net (code "40") (name "PWM_MT1B_SERVO1") (class "Default")
      (node (ref "GBA_CONNECTOR") (pin "P$16") (pinfunction "D0_P$16") (pintype "bidirectional"))
      (node (ref "SERVO1") (pin "3") (pinfunction "S_3") (pintype "passive"))
      (node (ref "U1") (pin "22") (pinfunction "AIN2_22") (pintype "bidirectional"))
    )
    (net (code "41") (name "PWM_MT2A_SERVO2") (class "Default")
      (node (ref "GBA_CONNECTOR") (pin "P$18") (pinfunction "D2_P$18") (pintype "bidirectional"))
      (node (ref "SERVO2") (pin "3") (pinfunction "S_3") (pintype "passive"))
      (node (ref "U1") (pin "17") (pinfunction "BIN1_17") (pintype "bidirectional"))
    )
    (net (code "42") (name "PWM_MT2B") (class "Default")
      (node (ref "GBA_CONNECTOR") (pin "P$19") (pinfunction "D3_P$19") (pintype "bidirectional"))
      (node (ref "U1") (pin "16") (pinfunction "BIN2_16") (pintype "bidirectional"))
    )
    (net (code "43") (name "PWM_MT3A") (class "Default")
      (node (ref "GBA_CONNECTOR") (pin "P$21") (pinfunction "D5_P$21") (pintype "bidirectional"))
      (node (ref "U3") (pin "21") (pinfunction "AIN1_21") (pintype "bidirectional"))
    )
    (net (code "44") (name "PWM_MT3B_SERVO3") (class "Default")
      (node (ref "GBA_CONNECTOR") (pin "P$20") (pinfunction "D4_P$20") (pintype "bidirectional"))
      (node (ref "SERVO3") (pin "3") (pinfunction "S_3") (pintype "passive"))
      (node (ref "U3") (pin "22") (pinfunction "AIN2_22") (pintype "bidirectional"))
    )
    (net (code "45") (name "PWM_MT4A_SERVO4") (class "Default")
      (node (ref "GBA_CONNECTOR") (pin "P$22") (pinfunction "D6_P$22") (pintype "bidirectional"))
      (node (ref "SERVO4") (pin "3") (pinfunction "S_3") (pintype "passive"))
      (node (ref "U3") (pin "17") (pinfunction "BIN1_17") (pintype "bidirectional"))
    )
    (net (code "46") (name "PWM_MT4B") (class "Default")
      (node (ref "GBA_CONNECTOR") (pin "P$23") (pinfunction "D7_P$23") (pintype "bidirectional"))
      (node (ref "U3") (pin "16") (pinfunction "BIN2_16") (pintype "bidirectional"))
    )
    (net (code "47") (name "PWM_MT5A") (class "Default")
      (node (ref "GBA_CONNECTOR") (pin "P$25") (pinfunction "D9_P$25") (pintype "bidirectional"))
      (node (ref "TB6621FNG") (pin "21") (pinfunction "AIN1_21") (pintype "bidirectional"))
    )
    (net (code "48") (name "PWM_MT5B_SERVO5") (class "Default")
      (node (ref "GBA_CONNECTOR") (pin "P$24") (pinfunction "D8_P$24") (pintype "bidirectional"))
      (node (ref "SERVO5") (pin "3") (pinfunction "S_3") (pintype "passive"))
      (node (ref "TB6621FNG") (pin "22") (pinfunction "AIN2_22") (pintype "bidirectional"))
    )
    (net (code "49") (name "PWM_MT6A_SERVO6") (class "Default")
      (node (ref "GBA_CONNECTOR") (pin "P$26") (pinfunction "D10_P$26") (pintype "bidirectional"))
      (node (ref "SERVO6") (pin "3") (pinfunction "S_3") (pintype "passive"))
      (node (ref "TB6621FNG") (pin "17") (pinfunction "BIN1_17") (pintype "bidirectional"))
    )
    (net (code "50") (name "PWM_MT6B") (class "Default")
      (node (ref "GBA_CONNECTOR") (pin "P$27") (pinfunction "D11_P$27") (pintype "bidirectional"))
      (node (ref "TB6621FNG") (pin "16") (pinfunction "BIN2_16") (pintype "bidirectional"))
    )
    (net (code "51") (name "SCL") (class "Default")
      (node (ref "FINGER1") (pin "4") (pinfunction "4_4") (pintype "bidirectional"))
      (node (ref "FINGER2") (pin "4") (pinfunction "4_4") (pintype "bidirectional"))
      (node (ref "FINGER3") (pin "4") (pinfunction "4_4") (pintype "bidirectional"))
      (node (ref "FINGER4") (pin "4") (pinfunction "4_4") (pintype "bidirectional"))
      (node (ref "FINGER5") (pin "4") (pinfunction "4_4") (pintype "bidirectional"))
      (node (ref "FINGER6") (pin "4") (pinfunction "4_4") (pintype "bidirectional"))
      (node (ref "FINGER7") (pin "4") (pinfunction "4_4") (pintype "bidirectional"))
      (node (ref "GBA_CONNECTOR") (pin "P$31") (pinfunction "I2C_SCL_P$31") (pintype "bidirectional"))
      (node (ref "INA219") (pin "5") (pinfunction "SCL_5") (pintype "bidirectional"))
      (node (ref "R5") (pin "2") (pinfunction "2_2") (pintype "passive"))
    )
    (net (code "52") (name "SDA") (class "Default")
      (node (ref "FINGER1") (pin "5") (pinfunction "5_5") (pintype "bidirectional"))
      (node (ref "FINGER2") (pin "5") (pinfunction "5_5") (pintype "bidirectional"))
      (node (ref "FINGER3") (pin "5") (pinfunction "5_5") (pintype "bidirectional"))
      (node (ref "FINGER4") (pin "5") (pinfunction "5_5") (pintype "bidirectional"))
      (node (ref "FINGER5") (pin "5") (pinfunction "5_5") (pintype "bidirectional"))
      (node (ref "FINGER6") (pin "5") (pinfunction "5_5") (pintype "bidirectional"))
      (node (ref "FINGER7") (pin "5") (pinfunction "5_5") (pintype "bidirectional"))
      (node (ref "GBA_CONNECTOR") (pin "P$30") (pinfunction "I2C_SDA_P$30") (pintype "bidirectional"))
      (node (ref "INA219") (pin "6") (pinfunction "SDA_6") (pintype "bidirectional"))
      (node (ref "R4") (pin "2") (pinfunction "2_2") (pintype "passive"))
    )
    (net (code "53") (name "SOK") (class "Default")
      (node (ref "GBA_CONNECTOR") (pin "P$5") (pinfunction "SOK_P$5") (pintype "bidirectional"))
      (node (ref "R6") (pin "2") (pinfunction "2_2") (pintype "passive"))
      (node (ref "R7") (pin "1") (pinfunction "1_1") (pintype "passive"))
    )
    (net (code "54") (name "VBAT") (class "Default")
      (node (ref "5.0V_REGULATOR") (pin "2") (pinfunction "VIN_2") (pintype "bidirectional"))
      (node (ref "C19") (pin "1") (pinfunction "P$1_1") (pintype "passive"))
      (node (ref "INA219") (pin "2") (pinfunction "VIN-_2") (pintype "bidirectional"))
      (node (ref "INA_BYPASS") (pin "1") (pinfunction "1_1") (pintype "passive"))
      (node (ref "R18") (pin "2") (pinfunction "2_2") (pintype "passive"))
      (node (ref "R20") (pin "1") (pinfunction "1_1") (pintype "passive"))
    )
    (net (code "55") (name "VLIPO") (class "Default")
      (node (ref "BATTERY") (pin "3") (pinfunction "S_3") (pintype "passive"))
      (node (ref "INA219") (pin "1") (pinfunction "VIN+_1") (pintype "bidirectional"))
      (node (ref "INA_BYPASS") (pin "2") (pinfunction "2_2") (pintype "passive"))
      (node (ref "R20") (pin "2") (pinfunction "2_2") (pintype "passive"))
    )
    (net (code "56") (name "unconnected-(5.0V_REGULATOR-NC_1-Pad8)") (class "Default")
      (node (ref "5.0V_REGULATOR") (pin "8") (pinfunction "NC_1_8") (pintype "bidirectional"))
    )
    (net (code "57") (name "unconnected-(5.0V_REGULATOR-NC_2-Pad11)") (class "Default")
      (node (ref "5.0V_REGULATOR") (pin "11") (pinfunction "NC_2_11") (pintype "bidirectional"))
    )
    (net (code "58") (name "unconnected-(5.0V_REGULATOR-NC_3-Pad12)") (class "Default")
      (node (ref "5.0V_REGULATOR") (pin "12") (pinfunction "NC_3_12") (pintype "bidirectional"))
    )
    (net (code "59") (name "unconnected-(5.0V_REGULATOR-PG-Pad10)") (class "Default")
      (node (ref "5.0V_REGULATOR") (pin "10") (pinfunction "PG_10") (pintype "bidirectional"))
    )
    (net (code "60") (name "unconnected-(5.0V_REGULATOR-SEQ-Pad9)") (class "Default")
      (node (ref "5.0V_REGULATOR") (pin "9") (pinfunction "SEQ_9") (pintype "bidirectional"))
    )
    (net (code "61") (name "unconnected-(BATTERYB-S-Pad2)") (class "Default")
      (node (ref "BATTERY") (pin "2") (pinfunction "S_2") (pintype "passive"))
    )
    (net (code "62") (name "unconnected-(SW1-O-PadA)") (class "Default")
      (node (ref "SW1") (pin "A") (pinfunction "O_A") (pintype "passive"))
    )
  )
)
